# Smart_IOT_v1.net
KiCad netlist of a schematic drawn in EAGLE
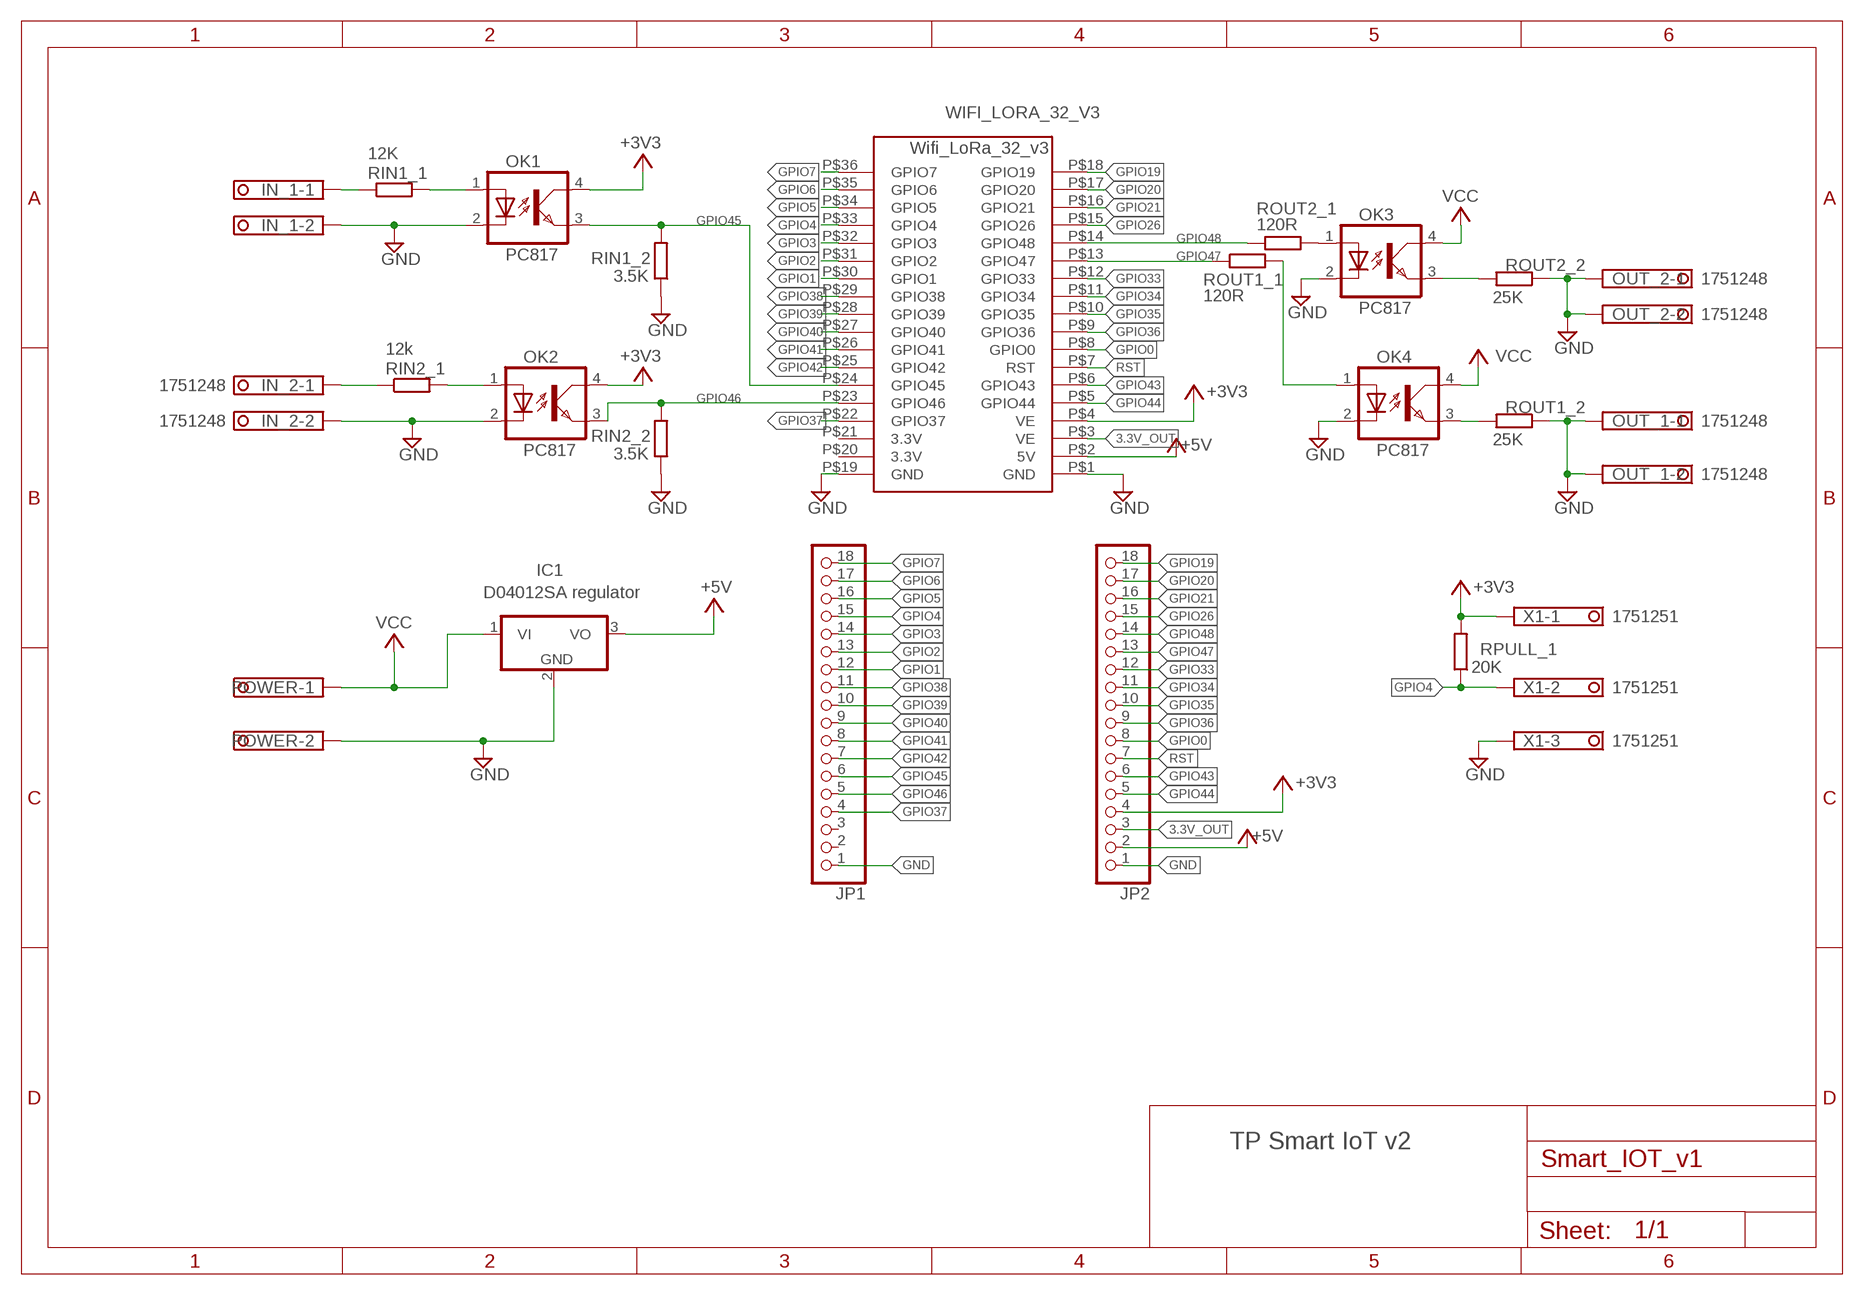
[diagram p0: schematic, sheet 1]

(export (version "E")
  (design (tool "Eeschema 10.0.6"))
  (components
    (comp (ref "IC1")
      (value "7805TV")
      (footprint "eagle-import:TO220V")
      (libsource (lib "eagle-import") (part "78TV05"))
    )
    (comp (ref "IN_1")
      (value "1751248")
      (footprint "eagle-import:1751248")
      (libsource (lib "eagle-import") (part "1751248"))
    )
    (comp (ref "IN_2")
      (value "1751248")
      (footprint "eagle-import:1751248")
      (libsource (lib "eagle-import") (part "1751248"))
    )
    (comp (ref "JP1")
      (value "PINHD-1X18")
      (footprint "eagle-import:1X18")
      (libsource (lib "eagle-import") (part "PINHD-1X18"))
    )
    (comp (ref "JP2")
      (value "PINHD-1X18")
      (footprint "eagle-import:1X18")
      (libsource (lib "eagle-import") (part "PINHD-1X18"))
    )
    (comp (ref "OK1")
      (value "PC817")
      (footprint "eagle-import:DIL04")
      (fields (field (name "MPN") "PC817X4J000F"))
      (libsource (lib "eagle-import") (part "PC817"))
    )
    (comp (ref "OK2")
      (value "PC817")
      (footprint "eagle-import:DIL04")
      (fields (field (name "MPN") "PC817X4J000F"))
      (libsource (lib "eagle-import") (part "PC817"))
    )
    (comp (ref "OK3")
      (value "PC817")
      (footprint "eagle-import:DIL04")
      (fields (field (name "MPN") "PC817X4J000F"))
      (libsource (lib "eagle-import") (part "PC817"))
    )
    (comp (ref "OK4")
      (value "PC817")
      (footprint "eagle-import:DIL04")
      (fields (field (name "MPN") "PC817X4J000F"))
      (libsource (lib "eagle-import") (part "PC817"))
    )
    (comp (ref "OUT_1")
      (value "1751248")
      (footprint "eagle-import:1751248")
      (libsource (lib "eagle-import") (part "1751248"))
    )
    (comp (ref "OUT_2")
      (value "1751248")
      (footprint "eagle-import:1751248")
      (libsource (lib "eagle-import") (part "1751248"))
    )
    (comp (ref "POWER")
      (value "1751248")
      (footprint "eagle-import:1751248")
      (libsource (lib "eagle-import") (part "1751248"))
    )
    (comp (ref "RIN1_1")
      (value "12K")
      (footprint "eagle-import:M1206")
      (libsource (lib "eagle-import") (part "R-EU_M1206"))
    )
    (comp (ref "RIN1_2")
      (value "3.5K")
      (footprint "eagle-import:M1206")
      (libsource (lib "eagle-import") (part "R-EU_M1206"))
    )
    (comp (ref "RIN2_1")
      (value "12k")
      (footprint "eagle-import:M1206")
      (libsource (lib "eagle-import") (part "R-EU_M1206"))
    )
    (comp (ref "RIN2_2")
      (value "3.5K")
      (footprint "eagle-import:M1206")
      (libsource (lib "eagle-import") (part "R-EU_M1206"))
    )
    (comp (ref "ROUT1_1")
      (value "120R")
      (footprint "eagle-import:M1206")
      (libsource (lib "eagle-import") (part "R-EU_M1206"))
    )
    (comp (ref "ROUT1_2")
      (value "25K")
      (footprint "eagle-import:M1206")
      (libsource (lib "eagle-import") (part "R-EU_M1206"))
    )
    (comp (ref "ROUT2_1")
      (value "120R")
      (footprint "eagle-import:M1206")
      (libsource (lib "eagle-import") (part "R-EU_M1206"))
    )
    (comp (ref "ROUT2_2")
      (value "25K")
      (footprint "eagle-import:M1206")
      (libsource (lib "eagle-import") (part "R-EU_M1206"))
    )
    (comp (ref "RPULL_1")
      (value "20K")
      (footprint "eagle-import:M1206")
      (libsource (lib "eagle-import") (part "R-EU_M1206"))
    )
    (comp (ref "WIFI_LORA_32_V3")
      (value "WIFI_LORA_32_V3")
      (footprint "eagle-import:WIFI_LORA_32_V3")
      (libsource (lib "eagle-import") (part "WIFI_LORA_32_V3"))
    )
    (comp (ref "X1")
      (value "1751251")
      (footprint "eagle-import:1751251")
      (libsource (lib "eagle-import") (part "1751251"))
    )
  )
  (nets
    (net (code "1") (name "+3V3") (class "Default")
      (node (ref "JP2") (pin "4") (pinfunction "4_4") (pintype "passive"))
      (node (ref "OK1") (pin "4") (pinfunction "COL_4") (pintype "passive"))
      (node (ref "OK2") (pin "4") (pinfunction "COL_4") (pintype "passive"))
      (node (ref "RPULL_1") (pin "2") (pinfunction "2_2") (pintype "passive"))
      (node (ref "WIFI_LORA_32_V3") (pin "P$4") (pinfunction "VE_P$4") (pintype "bidirectional"))
      (node (ref "X1") (pin "1") (pinfunction "K_1") (pintype "passive"))
    )
    (net (code "2") (name "+5V") (class "Default")
      (node (ref "IC1") (pin "3") (pinfunction "VO_3") (pintype "passive"))
      (node (ref "JP2") (pin "2") (pinfunction "2_2") (pintype "passive"))
      (node (ref "WIFI_LORA_32_V3") (pin "P$2") (pinfunction "5V_P$2") (pintype "bidirectional"))
    )
    (net (code "3") (name "3.3V_OUT") (class "Default")
      (node (ref "JP2") (pin "3") (pinfunction "3_3") (pintype "passive"))
      (node (ref "WIFI_LORA_32_V3") (pin "P$3") (pinfunction "VE_P$3") (pintype "bidirectional"))
    )
    (net (code "4") (name "GND") (class "Default")
      (node (ref "IC1") (pin "2") (pinfunction "GND_2") (pintype "passive"))
      (node (ref "IN_1") (pin "2") (pinfunction "K_2") (pintype "passive"))
      (node (ref "IN_2") (pin "2") (pinfunction "K_2") (pintype "passive"))
      (node (ref "JP1") (pin "1") (pinfunction "1_1") (pintype "passive"))
      (node (ref "JP2") (pin "1") (pinfunction "1_1") (pintype "passive"))
      (node (ref "OK1") (pin "2") (pinfunction "C_2") (pintype "passive"))
      (node (ref "OK2") (pin "2") (pinfunction "C_2") (pintype "passive"))
      (node (ref "OK3") (pin "2") (pinfunction "C_2") (pintype "passive"))
      (node (ref "OK4") (pin "2") (pinfunction "C_2") (pintype "passive"))
      (node (ref "OUT_1") (pin "1") (pinfunction "K_1") (pintype "passive"))
      (node (ref "OUT_1") (pin "2") (pinfunction "K_2") (pintype "passive"))
      (node (ref "OUT_2") (pin "1") (pinfunction "K_1") (pintype "passive"))
      (node (ref "OUT_2") (pin "2") (pinfunction "K_2") (pintype "passive"))
      (node (ref "POWER") (pin "2") (pinfunction "K_2") (pintype "passive"))
      (node (ref "RIN1_2") (pin "1") (pinfunction "1_1") (pintype "passive"))
      (node (ref "RIN2_2") (pin "1") (pinfunction "1_1") (pintype "passive"))
      (node (ref "ROUT1_2") (pin "1") (pinfunction "1_1") (pintype "passive"))
      (node (ref "ROUT2_2") (pin "1") (pinfunction "1_1") (pintype "passive"))
      (node (ref "WIFI_LORA_32_V3") (pin "P$1") (pinfunction "GND_P$1") (pintype "bidirectional"))
      (node (ref "WIFI_LORA_32_V3") (pin "P$19") (pinfunction "GND_P$19") (pintype "bidirectional"))
      (node (ref "X1") (pin "3") (pinfunction "K_3") (pintype "passive"))
    )
    (net (code "5") (name "GPIO0") (class "Default")
      (node (ref "JP2") (pin "8") (pinfunction "8_8") (pintype "passive"))
      (node (ref "WIFI_LORA_32_V3") (pin "P$8") (pinfunction "GPIO0_P$8") (pintype "bidirectional"))
    )
    (net (code "6") (name "GPIO1") (class "Default")
      (node (ref "JP1") (pin "12") (pinfunction "12_12") (pintype "passive"))
      (node (ref "WIFI_LORA_32_V3") (pin "P$30") (pinfunction "GPIO1_P$30") (pintype "bidirectional"))
    )
    (net (code "7") (name "GPIO2") (class "Default")
      (node (ref "JP1") (pin "13") (pinfunction "13_13") (pintype "passive"))
      (node (ref "WIFI_LORA_32_V3") (pin "P$31") (pinfunction "GPIO2_P$31") (pintype "bidirectional"))
    )
    (net (code "8") (name "GPIO3") (class "Default")
      (node (ref "JP1") (pin "14") (pinfunction "14_14") (pintype "passive"))
      (node (ref "WIFI_LORA_32_V3") (pin "P$32") (pinfunction "GPIO3_P$32") (pintype "bidirectional"))
    )
    (net (code "9") (name "GPIO4") (class "Default")
      (node (ref "JP1") (pin "15") (pinfunction "15_15") (pintype "passive"))
      (node (ref "RPULL_1") (pin "1") (pinfunction "1_1") (pintype "passive"))
      (node (ref "WIFI_LORA_32_V3") (pin "P$33") (pinfunction "GPIO4_P$33") (pintype "bidirectional"))
      (node (ref "X1") (pin "2") (pinfunction "K_2") (pintype "passive"))
    )
    (net (code "10") (name "GPIO5") (class "Default")
      (node (ref "JP1") (pin "16") (pinfunction "16_16") (pintype "passive"))
      (node (ref "WIFI_LORA_32_V3") (pin "P$34") (pinfunction "GPIO5_P$34") (pintype "bidirectional"))
    )
    (net (code "11") (name "GPIO6") (class "Default")
      (node (ref "JP1") (pin "17") (pinfunction "17_17") (pintype "passive"))
      (node (ref "WIFI_LORA_32_V3") (pin "P$35") (pinfunction "GPIO6_P$35") (pintype "bidirectional"))
    )
    (net (code "12") (name "GPIO7") (class "Default")
      (node (ref "JP1") (pin "18") (pinfunction "18_18") (pintype "passive"))
      (node (ref "WIFI_LORA_32_V3") (pin "P$36") (pinfunction "GPIO7_P$36") (pintype "bidirectional"))
    )
    (net (code "13") (name "GPIO19") (class "Default")
      (node (ref "JP2") (pin "18") (pinfunction "18_18") (pintype "passive"))
      (node (ref "WIFI_LORA_32_V3") (pin "P$18") (pinfunction "GPIO19_P$18") (pintype "bidirectional"))
    )
    (net (code "14") (name "GPIO20") (class "Default")
      (node (ref "JP2") (pin "17") (pinfunction "17_17") (pintype "passive"))
      (node (ref "WIFI_LORA_32_V3") (pin "P$17") (pinfunction "GPIO20_P$17") (pintype "bidirectional"))
    )
    (net (code "15") (name "GPIO21") (class "Default")
      (node (ref "JP2") (pin "16") (pinfunction "16_16") (pintype "passive"))
      (node (ref "WIFI_LORA_32_V3") (pin "P$16") (pinfunction "GPIO21_P$16") (pintype "bidirectional"))
    )
    (net (code "16") (name "GPIO26") (class "Default")
      (node (ref "JP2") (pin "15") (pinfunction "15_15") (pintype "passive"))
      (node (ref "WIFI_LORA_32_V3") (pin "P$15") (pinfunction "GPIO26_P$15") (pintype "bidirectional"))
    )
    (net (code "17") (name "GPIO33") (class "Default")
      (node (ref "JP2") (pin "12") (pinfunction "12_12") (pintype "passive"))
      (node (ref "WIFI_LORA_32_V3") (pin "P$12") (pinfunction "GPIO33_P$12") (pintype "bidirectional"))
    )
    (net (code "18") (name "GPIO34") (class "Default")
      (node (ref "JP2") (pin "11") (pinfunction "11_11") (pintype "passive"))
      (node (ref "WIFI_LORA_32_V3") (pin "P$11") (pinfunction "GPIO34_P$11") (pintype "bidirectional"))
    )
    (net (code "19") (name "GPIO35") (class "Default")
      (node (ref "JP2") (pin "10") (pinfunction "10_10") (pintype "passive"))
      (node (ref "WIFI_LORA_32_V3") (pin "P$10") (pinfunction "GPIO35_P$10") (pintype "bidirectional"))
    )
    (net (code "20") (name "GPIO36") (class "Default")
      (node (ref "JP2") (pin "9") (pinfunction "9_9") (pintype "passive"))
      (node (ref "WIFI_LORA_32_V3") (pin "P$9") (pinfunction "GPIO36_P$9") (pintype "bidirectional"))
    )
    (net (code "21") (name "GPIO37") (class "Default")
      (node (ref "JP1") (pin "4") (pinfunction "4_4") (pintype "passive"))
      (node (ref "WIFI_LORA_32_V3") (pin "P$22") (pinfunction "GPIO37_P$22") (pintype "bidirectional"))
    )
    (net (code "22") (name "GPIO38") (class "Default")
      (node (ref "JP1") (pin "11") (pinfunction "11_11") (pintype "passive"))
      (node (ref "WIFI_LORA_32_V3") (pin "P$29") (pinfunction "GPIO38_P$29") (pintype "bidirectional"))
    )
    (net (code "23") (name "GPIO39") (class "Default")
      (node (ref "JP1") (pin "10") (pinfunction "10_10") (pintype "passive"))
      (node (ref "WIFI_LORA_32_V3") (pin "P$28") (pinfunction "GPIO39_P$28") (pintype "bidirectional"))
    )
    (net (code "24") (name "GPIO40") (class "Default")
      (node (ref "JP1") (pin "9") (pinfunction "9_9") (pintype "passive"))
      (node (ref "WIFI_LORA_32_V3") (pin "P$27") (pinfunction "GPIO40_P$27") (pintype "bidirectional"))
    )
    (net (code "25") (name "GPIO41") (class "Default")
      (node (ref "JP1") (pin "8") (pinfunction "8_8") (pintype "passive"))
      (node (ref "WIFI_LORA_32_V3") (pin "P$26") (pinfunction "GPIO41_P$26") (pintype "bidirectional"))
    )
    (net (code "26") (name "GPIO42") (class "Default")
      (node (ref "JP1") (pin "7") (pinfunction "7_7") (pintype "passive"))
      (node (ref "WIFI_LORA_32_V3") (pin "P$25") (pinfunction "GPIO42_P$25") (pintype "bidirectional"))
    )
    (net (code "27") (name "GPIO43") (class "Default")
      (node (ref "JP2") (pin "6") (pinfunction "6_6") (pintype "passive"))
      (node (ref "WIFI_LORA_32_V3") (pin "P$6") (pinfunction "GPIO43_P$6") (pintype "bidirectional"))
    )
    (net (code "28") (name "GPIO44") (class "Default")
      (node (ref "JP2") (pin "5") (pinfunction "5_5") (pintype "passive"))
      (node (ref "WIFI_LORA_32_V3") (pin "P$5") (pinfunction "GPIO44_P$5") (pintype "bidirectional"))
    )
    (net (code "29") (name "GPIO45") (class "Default")
      (node (ref "JP1") (pin "6") (pinfunction "6_6") (pintype "passive"))
      (node (ref "OK1") (pin "3") (pinfunction "EMIT_3") (pintype "passive"))
      (node (ref "RIN1_2") (pin "2") (pinfunction "2_2") (pintype "passive"))
      (node (ref "WIFI_LORA_32_V3") (pin "P$24") (pinfunction "GPIO45_P$24") (pintype "bidirectional"))
    )
    (net (code "30") (name "GPIO46") (class "Default")
      (node (ref "JP1") (pin "5") (pinfunction "5_5") (pintype "passive"))
      (node (ref "OK2") (pin "3") (pinfunction "EMIT_3") (pintype "passive"))
      (node (ref "RIN2_2") (pin "2") (pinfunction "2_2") (pintype "passive"))
      (node (ref "WIFI_LORA_32_V3") (pin "P$23") (pinfunction "GPIO46_P$23") (pintype "bidirectional"))
    )
    (net (code "31") (name "GPIO47") (class "Default")
      (node (ref "JP2") (pin "13") (pinfunction "13_13") (pintype "passive"))
      (node (ref "ROUT1_1") (pin "1") (pinfunction "1_1") (pintype "passive"))
      (node (ref "WIFI_LORA_32_V3") (pin "P$13") (pinfunction "GPIO47_P$13") (pintype "bidirectional"))
    )
    (net (code "32") (name "GPIO48") (class "Default")
      (node (ref "JP2") (pin "14") (pinfunction "14_14") (pintype "passive"))
      (node (ref "ROUT2_1") (pin "1") (pinfunction "1_1") (pintype "passive"))
      (node (ref "WIFI_LORA_32_V3") (pin "P$14") (pinfunction "GPIO48_P$14") (pintype "bidirectional"))
    )
    (net (code "33") (name "Net-(IN_1A-K)") (class "Default")
      (node (ref "IN_1") (pin "1") (pinfunction "K_1") (pintype "passive"))
      (node (ref "RIN1_1") (pin "1") (pinfunction "1_1") (pintype "passive"))
    )
    (net (code "34") (name "Net-(IN_2A-K)") (class "Default")
      (node (ref "IN_2") (pin "1") (pinfunction "K_1") (pintype "passive"))
      (node (ref "RIN2_1") (pin "1") (pinfunction "1_1") (pintype "passive"))
    )
    (net (code "35") (name "Net-(OK1-A)") (class "Default")
      (node (ref "OK1") (pin "1") (pinfunction "A_1") (pintype "passive"))
      (node (ref "RIN1_1") (pin "2") (pinfunction "2_2") (pintype "passive"))
    )
    (net (code "36") (name "Net-(OK2-A)") (class "Default")
      (node (ref "OK2") (pin "1") (pinfunction "A_1") (pintype "passive"))
      (node (ref "RIN2_1") (pin "2") (pinfunction "2_2") (pintype "passive"))
    )
    (net (code "37") (name "Net-(OK3-A)") (class "Default")
      (node (ref "OK3") (pin "1") (pinfunction "A_1") (pintype "passive"))
      (node (ref "ROUT2_1") (pin "2") (pinfunction "2_2") (pintype "passive"))
    )
    (net (code "38") (name "Net-(OK3-EMIT)") (class "Default")
      (node (ref "OK3") (pin "3") (pinfunction "EMIT_3") (pintype "passive"))
      (node (ref "ROUT2_2") (pin "2") (pinfunction "2_2") (pintype "passive"))
    )
    (net (code "39") (name "Net-(OK4-A)") (class "Default")
      (node (ref "OK4") (pin "1") (pinfunction "A_1") (pintype "passive"))
      (node (ref "ROUT1_1") (pin "2") (pinfunction "2_2") (pintype "passive"))
    )
    (net (code "40") (name "Net-(OK4-EMIT)") (class "Default")
      (node (ref "OK4") (pin "3") (pinfunction "EMIT_3") (pintype "passive"))
      (node (ref "ROUT1_2") (pin "2") (pinfunction "2_2") (pintype "passive"))
    )
    (net (code "41") (name "RST") (class "Default")
      (node (ref "JP2") (pin "7") (pinfunction "7_7") (pintype "passive"))
      (node (ref "WIFI_LORA_32_V3") (pin "P$7") (pinfunction "RST_P$7") (pintype "bidirectional"))
    )
    (net (code "42") (name "VCC") (class "Default")
      (node (ref "IC1") (pin "1") (pinfunction "VI_1") (pintype "input"))
      (node (ref "OK3") (pin "4") (pinfunction "COL_4") (pintype "passive"))
      (node (ref "OK4") (pin "4") (pinfunction "COL_4") (pintype "passive"))
      (node (ref "POWER") (pin "1") (pinfunction "K_1") (pintype "passive"))
    )
    (net (code "43") (name "unconnected-(JP1-Pad2)") (class "Default")
      (node (ref "JP1") (pin "2") (pinfunction "2_2") (pintype "passive"))
    )
    (net (code "44") (name "unconnected-(JP1-Pad3)") (class "Default")
      (node (ref "JP1") (pin "3") (pinfunction "3_3") (pintype "passive"))
    )
    (net (code "45") (name "unconnected-(WIFI_LORA_32_V3-3.3V-PadP$20)") (class "Default")
      (node (ref "WIFI_LORA_32_V3") (pin "P$20") (pinfunction "3.3V_P$20") (pintype "bidirectional"))
    )
    (net (code "46") (name "unconnected-(WIFI_LORA_32_V3-3.3V-PadP$21)") (class "Default")
      (node (ref "WIFI_LORA_32_V3") (pin "P$21") (pinfunction "3.3V_P$21") (pintype "bidirectional"))
    )
  )
)
